# 2xVCA_SMD.net
KiCad netlist of a schematic drawn in EAGLE
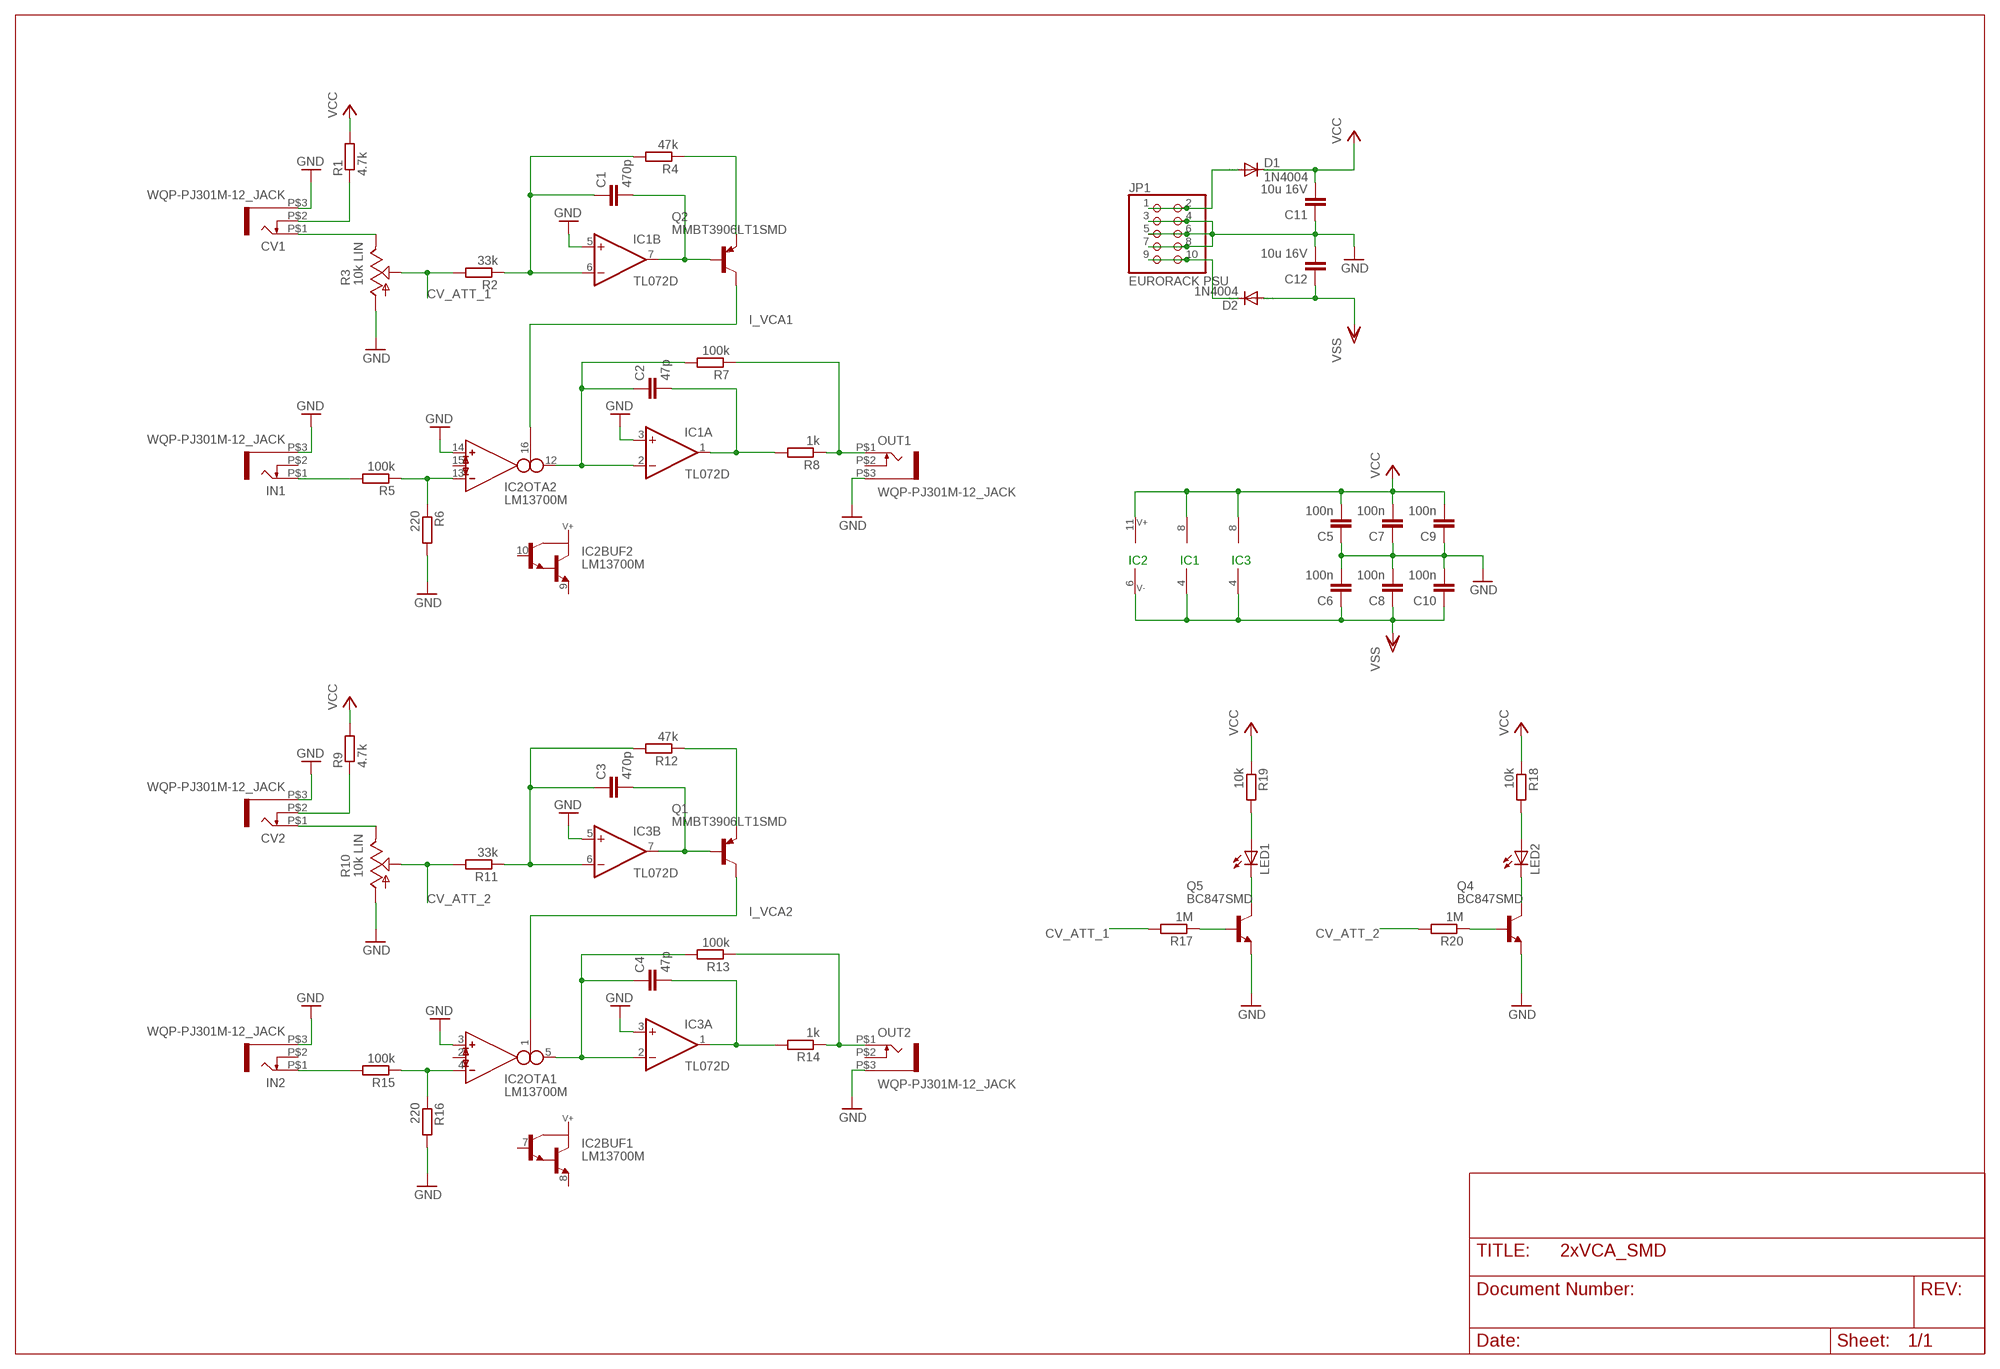
[diagram p0: schematic, sheet 1]

(export (version "E")
  (design (tool "Eeschema 10.0.6"))
  (components
    (comp (ref "C1")
      (value "470p")
      (footprint "eagle-import:C0603K")
      (libsource (lib "eagle-import") (part "C-EUC0603K"))
    )
    (comp (ref "C2")
      (value "47p")
      (footprint "eagle-import:C0603K")
      (libsource (lib "eagle-import") (part "C-EUC0603K"))
    )
    (comp (ref "C3")
      (value "470p")
      (footprint "eagle-import:C0603K")
      (libsource (lib "eagle-import") (part "C-EUC0603K"))
    )
    (comp (ref "C4")
      (value "47p")
      (footprint "eagle-import:C0603K")
      (libsource (lib "eagle-import") (part "C-EUC0603K"))
    )
    (comp (ref "C5")
      (value "100n")
      (footprint "eagle-import:C0603K")
      (libsource (lib "eagle-import") (part "C-EUC0603K"))
    )
    (comp (ref "C6")
      (value "100n")
      (footprint "eagle-import:C0603K")
      (libsource (lib "eagle-import") (part "C-EUC0603K"))
    )
    (comp (ref "C7")
      (value "100n")
      (footprint "eagle-import:C0603K")
      (libsource (lib "eagle-import") (part "C-EUC0603K"))
    )
    (comp (ref "C8")
      (value "100n")
      (footprint "eagle-import:C0603K")
      (libsource (lib "eagle-import") (part "C-EUC0603K"))
    )
    (comp (ref "C9")
      (value "100n")
      (footprint "eagle-import:C0603K")
      (libsource (lib "eagle-import") (part "C-EUC0603K"))
    )
    (comp (ref "C10")
      (value "100n")
      (footprint "eagle-import:C0603K")
      (libsource (lib "eagle-import") (part "C-EUC0603K"))
    )
    (comp (ref "C11")
      (value "10u 16V")
      (footprint "eagle-import:C1206K")
      (libsource (lib "eagle-import") (part "C-EUC1206K"))
    )
    (comp (ref "C12")
      (value "10u 16V")
      (footprint "eagle-import:C1206K")
      (libsource (lib "eagle-import") (part "C-EUC1206K"))
    )
    (comp (ref "CV1")
      (value "WQP-PJ301M-12_JACK")
      (footprint "eagle-import:WQP-PJ301M-12_JACK")
      (libsource (lib "eagle-import") (part "WQP-PJ301M-12_JACK"))
    )
    (comp (ref "CV2")
      (value "WQP-PJ301M-12_JACK")
      (footprint "eagle-import:WQP-PJ301M-12_JACK")
      (libsource (lib "eagle-import") (part "WQP-PJ301M-12_JACK"))
    )
    (comp (ref "D1")
      (value "1N4004")
      (footprint "eagle-import:DO214AA")
      (libsource (lib "eagle-import") (part "DIODE-DO214AA"))
    )
    (comp (ref "D2")
      (value "1N4004")
      (footprint "eagle-import:DO214AA")
      (libsource (lib "eagle-import") (part "DIODE-DO214AA"))
    )
    (comp (ref "IC1")
      (value "TL072D")
      (footprint "eagle-import:SO08")
      (libsource (lib "eagle-import") (part "TL072D"))
    )
    (comp (ref "IC2")
      (value "LM13700M")
      (footprint "eagle-import:SO16")
      (libsource (lib "eagle-import") (part "LM13700M"))
    )
    (comp (ref "IC3")
      (value "TL072D")
      (footprint "eagle-import:SO08")
      (libsource (lib "eagle-import") (part "TL072D"))
    )
    (comp (ref "IN1")
      (value "WQP-PJ301M-12_JACK")
      (footprint "eagle-import:WQP-PJ301M-12_JACK")
      (libsource (lib "eagle-import") (part "WQP-PJ301M-12_JACK"))
    )
    (comp (ref "IN2")
      (value "WQP-PJ301M-12_JACK")
      (footprint "eagle-import:WQP-PJ301M-12_JACK")
      (libsource (lib "eagle-import") (part "WQP-PJ301M-12_JACK"))
    )
    (comp (ref "JP1")
      (value "EURORACK PSU")
      (footprint "eagle-import:2X05")
      (libsource (lib "eagle-import") (part "PINHD-2X5"))
    )
    (comp (ref "LED1")
      (value "LED3MM")
      (footprint "eagle-import:LED3MM")
      (libsource (lib "eagle-import") (part "LED3MM"))
    )
    (comp (ref "LED2")
      (value "LED3MM")
      (footprint "eagle-import:LED3MM")
      (libsource (lib "eagle-import") (part "LED3MM"))
    )
    (comp (ref "OUT1")
      (value "WQP-PJ301M-12_JACK")
      (footprint "eagle-import:WQP-PJ301M-12_JACK")
      (libsource (lib "eagle-import") (part "WQP-PJ301M-12_JACK"))
    )
    (comp (ref "OUT2")
      (value "WQP-PJ301M-12_JACK")
      (footprint "eagle-import:WQP-PJ301M-12_JACK")
      (libsource (lib "eagle-import") (part "WQP-PJ301M-12_JACK"))
    )
    (comp (ref "Q1")
      (value "MMBT3906LT1SMD")
      (footprint "eagle-import:SOT23-BEC")
      (libsource (lib "eagle-import") (part "MMBT3906SMDLT1"))
    )
    (comp (ref "Q2")
      (value "MMBT3906LT1SMD")
      (footprint "eagle-import:SOT23-BEC")
      (libsource (lib "eagle-import") (part "MMBT3906SMDLT1"))
    )
    (comp (ref "Q4")
      (value "BC847SMD")
      (footprint "eagle-import:SOT23")
      (libsource (lib "eagle-import") (part "BC847SMD"))
    )
    (comp (ref "Q5")
      (value "BC847SMD")
      (footprint "eagle-import:SOT23")
      (libsource (lib "eagle-import") (part "BC847SMD"))
    )
    (comp (ref "R1")
      (value "4.7k")
      (footprint "eagle-import:R0603")
      (libsource (lib "eagle-import") (part "R-EU_R0603"))
    )
    (comp (ref "R2")
      (value "33k")
      (footprint "eagle-import:R0603")
      (libsource (lib "eagle-import") (part "R-EU_R0603"))
    )
    (comp (ref "R3")
      (value "10k LIN")
      (footprint "eagle-import:ALPS_POT_VERTICAL")
      (libsource (lib "eagle-import") (part "POT_USVERTICAL"))
    )
    (comp (ref "R4")
      (value "47k")
      (footprint "eagle-import:R0603")
      (libsource (lib "eagle-import") (part "R-EU_R0603"))
    )
    (comp (ref "R5")
      (value "100k")
      (footprint "eagle-import:R0603")
      (libsource (lib "eagle-import") (part "R-EU_R0603"))
    )
    (comp (ref "R6")
      (value "220")
      (footprint "eagle-import:R0603")
      (libsource (lib "eagle-import") (part "R-EU_R0603"))
    )
    (comp (ref "R7")
      (value "100k")
      (footprint "eagle-import:R0603")
      (libsource (lib "eagle-import") (part "R-EU_R0603"))
    )
    (comp (ref "R8")
      (value "1k")
      (footprint "eagle-import:R0603")
      (libsource (lib "eagle-import") (part "R-EU_R0603"))
    )
    (comp (ref "R9")
      (value "4.7k")
      (footprint "eagle-import:R0603")
      (libsource (lib "eagle-import") (part "R-EU_R0603"))
    )
    (comp (ref "R10")
      (value "10k LIN")
      (footprint "eagle-import:ALPS_POT_VERTICAL")
      (libsource (lib "eagle-import") (part "POT_USVERTICAL"))
    )
    (comp (ref "R11")
      (value "33k")
      (footprint "eagle-import:R0603")
      (libsource (lib "eagle-import") (part "R-EU_R0603"))
    )
    (comp (ref "R12")
      (value "47k")
      (footprint "eagle-import:R0603")
      (libsource (lib "eagle-import") (part "R-EU_R0603"))
    )
    (comp (ref "R13")
      (value "100k")
      (footprint "eagle-import:R0603")
      (libsource (lib "eagle-import") (part "R-EU_R0603"))
    )
    (comp (ref "R14")
      (value "1k")
      (footprint "eagle-import:R0603")
      (libsource (lib "eagle-import") (part "R-EU_R0603"))
    )
    (comp (ref "R15")
      (value "100k")
      (footprint "eagle-import:R0603")
      (libsource (lib "eagle-import") (part "R-EU_R0603"))
    )
    (comp (ref "R16")
      (value "220")
      (footprint "eagle-import:R0603")
      (libsource (lib "eagle-import") (part "R-EU_R0603"))
    )
    (comp (ref "R17")
      (value "1M")
      (footprint "eagle-import:R0603")
      (libsource (lib "eagle-import") (part "R-EU_R0603"))
    )
    (comp (ref "R18")
      (value "10k")
      (footprint "eagle-import:R0603")
      (libsource (lib "eagle-import") (part "R-EU_R0603"))
    )
    (comp (ref "R19")
      (value "10k")
      (footprint "eagle-import:R0603")
      (libsource (lib "eagle-import") (part "R-EU_R0603"))
    )
    (comp (ref "R20")
      (value "1M")
      (footprint "eagle-import:R0603")
      (libsource (lib "eagle-import") (part "R-EU_R0603"))
    )
  )
  (nets
    (net (code "1") (name "/CV_ATT_1") (class "Default")
      (node (ref "R17") (pin "2") (pinfunction "2_2") (pintype "passive"))
      (node (ref "R2") (pin "2") (pinfunction "2_2") (pintype "passive"))
      (node (ref "R3") (pin "P$2") (pinfunction "S_P$2") (pintype "passive"))
    )
    (net (code "2") (name "/CV_ATT_2") (class "Default")
      (node (ref "R10") (pin "P$2") (pinfunction "S_P$2") (pintype "passive"))
      (node (ref "R11") (pin "2") (pinfunction "2_2") (pintype "passive"))
      (node (ref "R20") (pin "2") (pinfunction "2_2") (pintype "passive"))
    )
    (net (code "3") (name "/I_VCA1") (class "Default")
      (node (ref "IC2") (pin "16") (pinfunction "I_BIAS_16") (pintype "input"))
      (node (ref "Q2") (pin "C") (pinfunction "C_C") (pintype "passive"))
    )
    (net (code "4") (name "/I_VCA2") (class "Default")
      (node (ref "IC2") (pin "1") (pinfunction "I_BIAS_1") (pintype "input"))
      (node (ref "Q1") (pin "C") (pinfunction "C_C") (pintype "passive"))
    )
    (net (code "5") (name "GND") (class "Default")
      (node (ref "C10") (pin "2") (pinfunction "2_2") (pintype "passive"))
      (node (ref "C11") (pin "1") (pinfunction "1_1") (pintype "passive"))
      (node (ref "C12") (pin "2") (pinfunction "2_2") (pintype "passive"))
      (node (ref "C5") (pin "1") (pinfunction "1_1") (pintype "passive"))
      (node (ref "C6") (pin "2") (pinfunction "2_2") (pintype "passive"))
      (node (ref "C7") (pin "1") (pinfunction "1_1") (pintype "passive"))
      (node (ref "C8") (pin "2") (pinfunction "2_2") (pintype "passive"))
      (node (ref "C9") (pin "1") (pinfunction "1_1") (pintype "passive"))
      (node (ref "CV1") (pin "P$3") (pinfunction "1_P$3") (pintype "passive"))
      (node (ref "CV2") (pin "P$3") (pinfunction "1_P$3") (pintype "passive"))
      (node (ref "IC1") (pin "3") (pinfunction "+IN_3") (pintype "input"))
      (node (ref "IC1") (pin "5") (pinfunction "+IN_5") (pintype "input"))
      (node (ref "IC2") (pin "14") (pinfunction "IN_P_14") (pintype "input"))
      (node (ref "IC2") (pin "3") (pinfunction "IN_P_3") (pintype "input"))
      (node (ref "IC3") (pin "3") (pinfunction "+IN_3") (pintype "input"))
      (node (ref "IC3") (pin "5") (pinfunction "+IN_5") (pintype "input"))
      (node (ref "IN1") (pin "P$3") (pinfunction "1_P$3") (pintype "passive"))
      (node (ref "IN2") (pin "P$3") (pinfunction "1_P$3") (pintype "passive"))
      (node (ref "JP1") (pin "3") (pinfunction "3_3") (pintype "passive"))
      (node (ref "JP1") (pin "4") (pinfunction "4_4") (pintype "passive"))
      (node (ref "JP1") (pin "5") (pinfunction "5_5") (pintype "passive"))
      (node (ref "JP1") (pin "6") (pinfunction "6_6") (pintype "passive"))
      (node (ref "JP1") (pin "7") (pinfunction "7_7") (pintype "passive"))
      (node (ref "JP1") (pin "8") (pinfunction "8_8") (pintype "passive"))
      (node (ref "OUT1") (pin "P$3") (pinfunction "1_P$3") (pintype "passive"))
      (node (ref "OUT2") (pin "P$3") (pinfunction "1_P$3") (pintype "passive"))
      (node (ref "Q4") (pin "2") (pinfunction "E_2") (pintype "passive"))
      (node (ref "Q5") (pin "2") (pinfunction "E_2") (pintype "passive"))
      (node (ref "R10") (pin "P$3") (pinfunction "A_P$3") (pintype "passive"))
      (node (ref "R16") (pin "2") (pinfunction "2_2") (pintype "passive"))
      (node (ref "R3") (pin "P$3") (pinfunction "A_P$3") (pintype "passive"))
      (node (ref "R6") (pin "2") (pinfunction "2_2") (pintype "passive"))
    )
    (net (code "6") (name "Net-(CV1-2)") (class "Default")
      (node (ref "CV1") (pin "P$1") (pinfunction "2_P$1") (pintype "passive"))
      (node (ref "R3") (pin "P$1") (pinfunction "E_P$1") (pintype "passive"))
    )
    (net (code "7") (name "Net-(CV1-3)") (class "Default")
      (node (ref "CV1") (pin "P$2") (pinfunction "3_P$2") (pintype "passive"))
      (node (ref "R1") (pin "1") (pinfunction "1_1") (pintype "passive"))
    )
    (net (code "8") (name "Net-(CV2-2)") (class "Default")
      (node (ref "CV2") (pin "P$1") (pinfunction "2_P$1") (pintype "passive"))
      (node (ref "R10") (pin "P$1") (pinfunction "E_P$1") (pintype "passive"))
    )
    (net (code "9") (name "Net-(CV2-3)") (class "Default")
      (node (ref "CV2") (pin "P$2") (pinfunction "3_P$2") (pintype "passive"))
      (node (ref "R9") (pin "1") (pinfunction "1_1") (pintype "passive"))
    )
    (net (code "10") (name "Net-(D1-PadA)") (class "Default")
      (node (ref "D1") (pin "A") (pinfunction "A_A") (pintype "passive"))
      (node (ref "JP1") (pin "1") (pinfunction "1_1") (pintype "passive"))
      (node (ref "JP1") (pin "2") (pinfunction "2_2") (pintype "passive"))
    )
    (net (code "11") (name "Net-(D2-PadC)") (class "Default")
      (node (ref "D2") (pin "C") (pinfunction "C_C") (pintype "passive"))
      (node (ref "JP1") (pin "10") (pinfunction "10_10") (pintype "passive"))
      (node (ref "JP1") (pin "9") (pinfunction "9_9") (pintype "passive"))
    )
    (net (code "12") (name "Net-(IC1A--IN)") (class "Default")
      (node (ref "C2") (pin "1") (pinfunction "1_1") (pintype "passive"))
      (node (ref "IC1") (pin "2") (pinfunction "-IN_2") (pintype "input"))
      (node (ref "IC2") (pin "12") (pinfunction "OUT_12") (pintype "output"))
      (node (ref "R7") (pin "2") (pinfunction "2_2") (pintype "passive"))
    )
    (net (code "13") (name "Net-(IC1A-OUT)") (class "Default")
      (node (ref "C2") (pin "2") (pinfunction "2_2") (pintype "passive"))
      (node (ref "IC1") (pin "1") (pinfunction "OUT_1") (pintype "output"))
      (node (ref "R8") (pin "2") (pinfunction "2_2") (pintype "passive"))
    )
    (net (code "14") (name "Net-(IC1B--IN)") (class "Default")
      (node (ref "C1") (pin "1") (pinfunction "1_1") (pintype "passive"))
      (node (ref "IC1") (pin "6") (pinfunction "-IN_6") (pintype "input"))
      (node (ref "R2") (pin "1") (pinfunction "1_1") (pintype "passive"))
      (node (ref "R4") (pin "2") (pinfunction "2_2") (pintype "passive"))
    )
    (net (code "15") (name "Net-(IC1B-OUT)") (class "Default")
      (node (ref "C1") (pin "2") (pinfunction "2_2") (pintype "passive"))
      (node (ref "IC1") (pin "7") (pinfunction "OUT_7") (pintype "output"))
      (node (ref "Q2") (pin "B") (pinfunction "B_B") (pintype "passive"))
    )
    (net (code "16") (name "Net-(IC2C-IN_N)") (class "Default")
      (node (ref "IC2") (pin "4") (pinfunction "IN_N_4") (pintype "input"))
      (node (ref "R15") (pin "1") (pinfunction "1_1") (pintype "passive"))
      (node (ref "R16") (pin "1") (pinfunction "1_1") (pintype "passive"))
    )
    (net (code "17") (name "Net-(IC2C-OUT)") (class "Default")
      (node (ref "C4") (pin "1") (pinfunction "1_1") (pintype "passive"))
      (node (ref "IC2") (pin "5") (pinfunction "OUT_5") (pintype "output"))
      (node (ref "IC3") (pin "2") (pinfunction "-IN_2") (pintype "input"))
      (node (ref "R13") (pin "2") (pinfunction "2_2") (pintype "passive"))
    )
    (net (code "18") (name "Net-(IC2D-IN_N)") (class "Default")
      (node (ref "IC2") (pin "13") (pinfunction "IN_N_13") (pintype "input"))
      (node (ref "R5") (pin "1") (pinfunction "1_1") (pintype "passive"))
      (node (ref "R6") (pin "1") (pinfunction "1_1") (pintype "passive"))
    )
    (net (code "19") (name "Net-(IC3A-OUT)") (class "Default")
      (node (ref "C4") (pin "2") (pinfunction "2_2") (pintype "passive"))
      (node (ref "IC3") (pin "1") (pinfunction "OUT_1") (pintype "output"))
      (node (ref "R14") (pin "2") (pinfunction "2_2") (pintype "passive"))
    )
    (net (code "20") (name "Net-(IC3B--IN)") (class "Default")
      (node (ref "C3") (pin "1") (pinfunction "1_1") (pintype "passive"))
      (node (ref "IC3") (pin "6") (pinfunction "-IN_6") (pintype "input"))
      (node (ref "R11") (pin "1") (pinfunction "1_1") (pintype "passive"))
      (node (ref "R12") (pin "2") (pinfunction "2_2") (pintype "passive"))
    )
    (net (code "21") (name "Net-(IC3B-OUT)") (class "Default")
      (node (ref "C3") (pin "2") (pinfunction "2_2") (pintype "passive"))
      (node (ref "IC3") (pin "7") (pinfunction "OUT_7") (pintype "output"))
      (node (ref "Q1") (pin "B") (pinfunction "B_B") (pintype "passive"))
    )
    (net (code "22") (name "Net-(IN1-2)") (class "Default")
      (node (ref "IN1") (pin "P$1") (pinfunction "2_P$1") (pintype "passive"))
      (node (ref "R5") (pin "2") (pinfunction "2_2") (pintype "passive"))
    )
    (net (code "23") (name "Net-(IN2-2)") (class "Default")
      (node (ref "IN2") (pin "P$1") (pinfunction "2_P$1") (pintype "passive"))
      (node (ref "R15") (pin "2") (pinfunction "2_2") (pintype "passive"))
    )
    (net (code "24") (name "Net-(LED1-C)") (class "Default")
      (node (ref "LED1") (pin "K") (pinfunction "C_K") (pintype "passive"))
      (node (ref "Q5") (pin "3") (pinfunction "C_3") (pintype "passive"))
    )
    (net (code "25") (name "Net-(LED1-PadA)") (class "Default")
      (node (ref "LED1") (pin "A") (pinfunction "A_A") (pintype "passive"))
      (node (ref "R19") (pin "2") (pinfunction "2_2") (pintype "passive"))
    )
    (net (code "26") (name "Net-(LED2-C)") (class "Default")
      (node (ref "LED2") (pin "K") (pinfunction "C_K") (pintype "passive"))
      (node (ref "Q4") (pin "3") (pinfunction "C_3") (pintype "passive"))
    )
    (net (code "27") (name "Net-(LED2-PadA)") (class "Default")
      (node (ref "LED2") (pin "A") (pinfunction "A_A") (pintype "passive"))
      (node (ref "R18") (pin "2") (pinfunction "2_2") (pintype "passive"))
    )
    (net (code "28") (name "Net-(OUT1-2)") (class "Default")
      (node (ref "OUT1") (pin "P$1") (pinfunction "2_P$1") (pintype "passive"))
      (node (ref "R7") (pin "1") (pinfunction "1_1") (pintype "passive"))
      (node (ref "R8") (pin "1") (pinfunction "1_1") (pintype "passive"))
    )
    (net (code "29") (name "Net-(OUT2-2)") (class "Default")
      (node (ref "OUT2") (pin "P$1") (pinfunction "2_P$1") (pintype "passive"))
      (node (ref "R13") (pin "1") (pinfunction "1_1") (pintype "passive"))
      (node (ref "R14") (pin "1") (pinfunction "1_1") (pintype "passive"))
    )
    (net (code "30") (name "Net-(Q1-PadE)") (class "Default")
      (node (ref "Q1") (pin "E") (pinfunction "E_E") (pintype "passive"))
      (node (ref "R12") (pin "1") (pinfunction "1_1") (pintype "passive"))
    )
    (net (code "31") (name "Net-(Q2-PadE)") (class "Default")
      (node (ref "Q2") (pin "E") (pinfunction "E_E") (pintype "passive"))
      (node (ref "R4") (pin "1") (pinfunction "1_1") (pintype "passive"))
    )
    (net (code "32") (name "Net-(Q4-B)") (class "Default")
      (node (ref "Q4") (pin "1") (pinfunction "B_1") (pintype "passive"))
      (node (ref "R20") (pin "1") (pinfunction "1_1") (pintype "passive"))
    )
    (net (code "33") (name "Net-(Q5-B)") (class "Default")
      (node (ref "Q5") (pin "1") (pinfunction "B_1") (pintype "passive"))
      (node (ref "R17") (pin "1") (pinfunction "1_1") (pintype "passive"))
    )
    (net (code "34") (name "VCC") (class "Default")
      (node (ref "C11") (pin "2") (pinfunction "2_2") (pintype "passive"))
      (node (ref "C5") (pin "2") (pinfunction "2_2") (pintype "passive"))
      (node (ref "C7") (pin "2") (pinfunction "2_2") (pintype "passive"))
      (node (ref "C9") (pin "2") (pinfunction "2_2") (pintype "passive"))
      (node (ref "D1") (pin "C") (pinfunction "C_C") (pintype "passive"))
      (node (ref "IC1") (pin "8") (pinfunction "V+_8") (pintype "power_in"))
      (node (ref "IC2") (pin "11") (pinfunction "V+_11") (pintype "power_in"))
      (node (ref "IC3") (pin "8") (pinfunction "V+_8") (pintype "power_in"))
      (node (ref "R1") (pin "2") (pinfunction "2_2") (pintype "passive"))
      (node (ref "R18") (pin "1") (pinfunction "1_1") (pintype "passive"))
      (node (ref "R19") (pin "1") (pinfunction "1_1") (pintype "passive"))
      (node (ref "R9") (pin "2") (pinfunction "2_2") (pintype "passive"))
    )
    (net (code "35") (name "VSS") (class "Default")
      (node (ref "C10") (pin "1") (pinfunction "1_1") (pintype "passive"))
      (node (ref "C12") (pin "1") (pinfunction "1_1") (pintype "passive"))
      (node (ref "C6") (pin "1") (pinfunction "1_1") (pintype "passive"))
      (node (ref "C8") (pin "1") (pinfunction "1_1") (pintype "passive"))
      (node (ref "D2") (pin "A") (pinfunction "A_A") (pintype "passive"))
      (node (ref "IC1") (pin "4") (pinfunction "V-_4") (pintype "power_in"))
      (node (ref "IC2") (pin "6") (pinfunction "V-_6") (pintype "power_in"))
      (node (ref "IC3") (pin "4") (pinfunction "V-_4") (pintype "power_in"))
    )
    (net (code "36") (name "unconnected-(IC2A-B-Pad7)") (class "Default")
      (node (ref "IC2") (pin "7") (pinfunction "B_7") (pintype "passive"))
    )
    (net (code "37") (name "unconnected-(IC2A-E-Pad8)") (class "Default")
      (node (ref "IC2") (pin "8") (pinfunction "E_8") (pintype "passive"))
    )
    (net (code "38") (name "unconnected-(IC2B-B-Pad10)") (class "Default")
      (node (ref "IC2") (pin "10") (pinfunction "B_10") (pintype "passive"))
    )
    (net (code "39") (name "unconnected-(IC2B-E-Pad9)") (class "Default")
      (node (ref "IC2") (pin "9") (pinfunction "E_9") (pintype "passive"))
    )
    (net (code "40") (name "unconnected-(IC2C-I_DIODE-Pad2)") (class "Default")
      (node (ref "IC2") (pin "2") (pinfunction "I_DIODE_2") (pintype "input"))
    )
    (net (code "41") (name "unconnected-(IC2D-I_DIODE-Pad15)") (class "Default")
      (node (ref "IC2") (pin "15") (pinfunction "I_DIODE_15") (pintype "input"))
    )
    (net (code "42") (name "unconnected-(IN1-3-PadP$2)") (class "Default")
      (node (ref "IN1") (pin "P$2") (pinfunction "3_P$2") (pintype "passive"))
    )
    (net (code "43") (name "unconnected-(IN2-3-PadP$2)") (class "Default")
      (node (ref "IN2") (pin "P$2") (pinfunction "3_P$2") (pintype "passive"))
    )
    (net (code "44") (name "unconnected-(OUT1-3-PadP$2)") (class "Default")
      (node (ref "OUT1") (pin "P$2") (pinfunction "3_P$2") (pintype "passive"))
    )
    (net (code "45") (name "unconnected-(OUT2-3-PadP$2)") (class "Default")
      (node (ref "OUT2") (pin "P$2") (pinfunction "3_P$2") (pintype "passive"))
    )
  )
)
